# ADC.net
KiCad netlist of a schematic drawn in Altium Designer
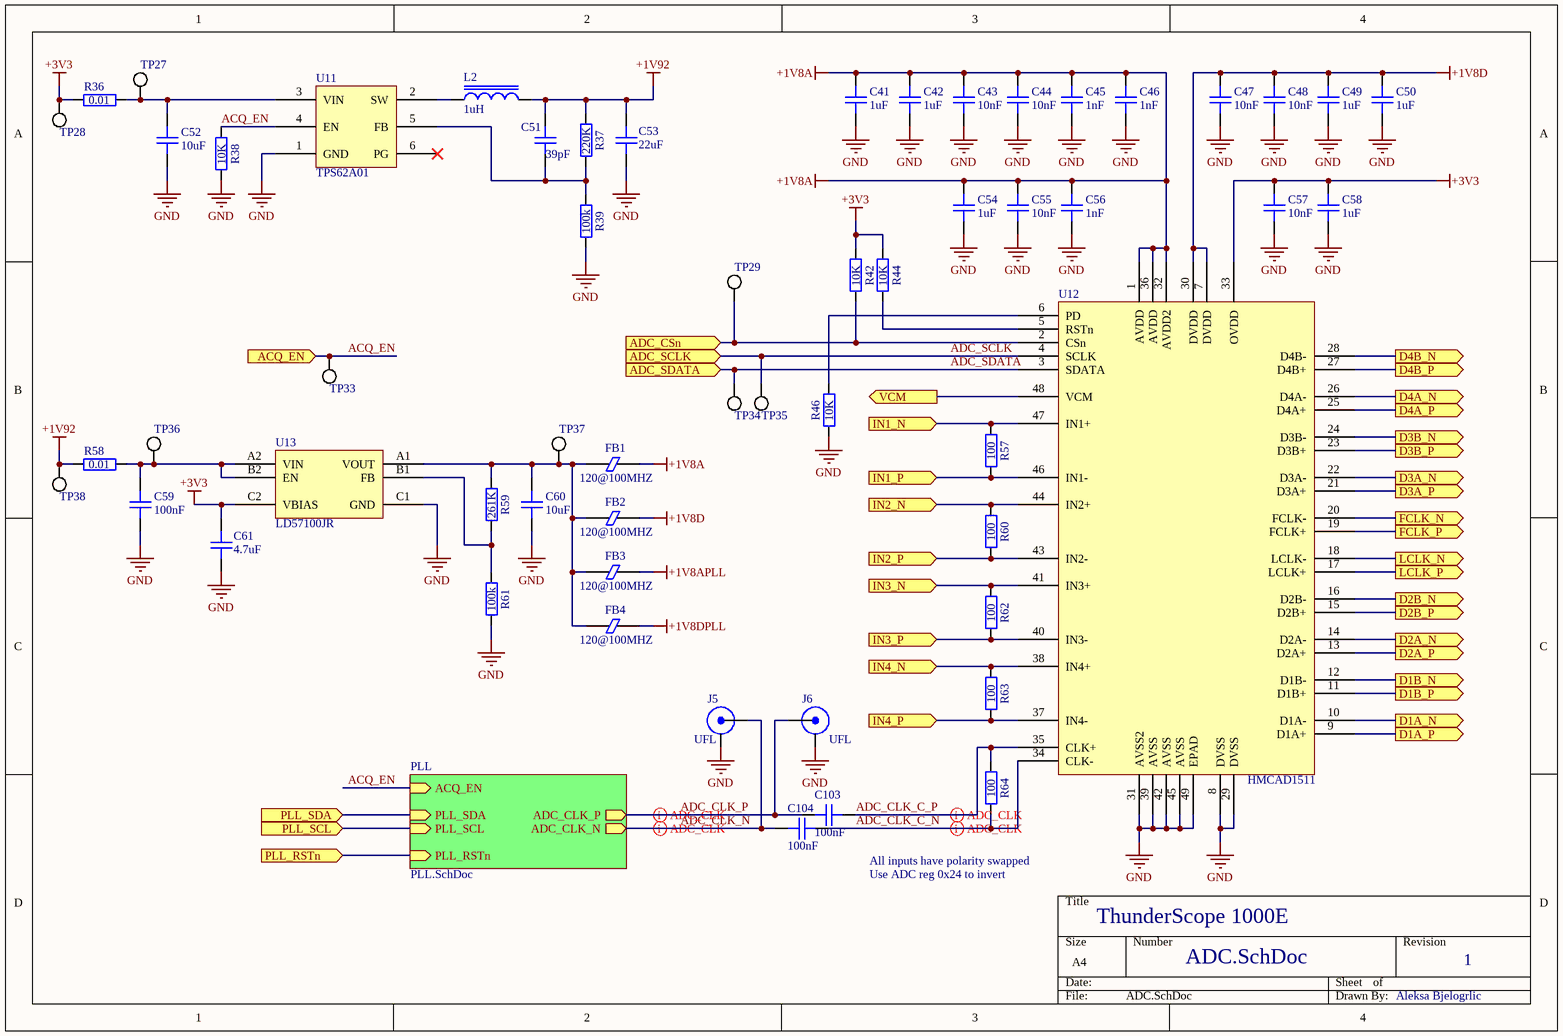
[diagram p0: ADC.SchDoc]

(export (version "E")
  (design (tool "Eeschema 10.0.6"))
  (components
    (comp (ref "C41")
      (value "1uF")
      (footprint "GEN_C_0402")
      (libsource (lib "DSO") (part "CAP 1uF 25V X5R 0402"))
    )
    (comp (ref "C42")
      (value "1uF")
      (footprint "GEN_C_0402")
      (libsource (lib "DSO") (part "CAP 1uF 25V X5R 0402"))
    )
    (comp (ref "C43")
      (value "10nF")
      (footprint "GEN_C_0402")
      (libsource (lib "DSO") (part "CAP 10nF 50V X7R 0402"))
    )
    (comp (ref "C44")
      (value "10nF")
      (footprint "GEN_C_0402")
      (libsource (lib "DSO") (part "CAP 10nF 50V X7R 0402"))
    )
    (comp (ref "C45")
      (value "1nF")
      (footprint "GEN_C_0402")
      (libsource (lib "DSO") (part "CAP 1nF 50V C0G 0402"))
    )
    (comp (ref "C46")
      (value "1nF")
      (footprint "GEN_C_0402")
      (libsource (lib "DSO") (part "CAP 1nF 50V C0G 0402"))
    )
    (comp (ref "C47")
      (value "10nF")
      (footprint "GEN_C_0402")
      (libsource (lib "DSO") (part "CAP 10nF 50V X7R 0402"))
    )
    (comp (ref "C48")
      (value "10nF")
      (footprint "GEN_C_0402")
      (libsource (lib "DSO") (part "CAP 10nF 50V X7R 0402"))
    )
    (comp (ref "C49")
      (value "1uF")
      (footprint "GEN_C_0402")
      (libsource (lib "DSO") (part "CAP 1uF 25V X5R 0402"))
    )
    (comp (ref "C50")
      (value "1uF")
      (footprint "GEN_C_0402")
      (libsource (lib "DSO") (part "CAP 1uF 25V X5R 0402"))
    )
    (comp (ref "C51")
      (value "39pF")
      (footprint "GEN_C_0402")
      (libsource (lib "DSO") (part "CAP 39pF 50V C0G 0402"))
    )
    (comp (ref "C52")
      (value "10uF")
      (footprint "GEN_C_0603")
      (libsource (lib "DSO") (part "CAP 10uF 10V X5R 0603"))
    )
    (comp (ref "C53")
      (value "22uF")
      (footprint "GEN_C_0805")
      (libsource (lib "DSO") (part "CAP 22uF 25V X5R 0805"))
    )
    (comp (ref "C54")
      (value "1uF")
      (footprint "GEN_C_0402")
      (libsource (lib "DSO") (part "CAP 1uF 25V X5R 0402"))
    )
    (comp (ref "C55")
      (value "10nF")
      (footprint "GEN_C_0402")
      (libsource (lib "DSO") (part "CAP 10nF 50V X7R 0402"))
    )
    (comp (ref "C56")
      (value "1nF")
      (footprint "GEN_C_0402")
      (libsource (lib "DSO") (part "CAP 1nF 50V C0G 0402"))
    )
    (comp (ref "C57")
      (value "10nF")
      (footprint "GEN_C_0402")
      (libsource (lib "DSO") (part "CAP 10nF 50V X7R 0402"))
    )
    (comp (ref "C58")
      (value "1uF")
      (footprint "GEN_C_0402")
      (libsource (lib "DSO") (part "CAP 1uF 25V X5R 0402"))
    )
    (comp (ref "C59")
      (value "100nF")
      (footprint "GEN_C_0402")
      (libsource (lib "DSO") (part "CAP 100nF 16V X7R 0402"))
    )
    (comp (ref "C60")
      (value "10uF")
      (footprint "GEN_C_0603")
      (libsource (lib "DSO") (part "CAP 10uF 10V X5R 0603"))
    )
    (comp (ref "C61")
      (value "4.7uF")
      (footprint "GEN_C_0402")
      (libsource (lib "DSO") (part "CAP 4.7uF 6.3V X5R 0402"))
    )
    (comp (ref "C103")
      (value "100nF")
      (footprint "GEN_C_0402")
      (libsource (lib "DSO") (part "CAP 100nF 16V X7R 0402"))
    )
    (comp (ref "C104")
      (value "100nF")
      (footprint "GEN_C_0402")
      (libsource (lib "DSO") (part "CAP 100nF 16V X7R 0402"))
    )
    (comp (ref "FB1")
      (value "120@100MHZ")
      (footprint "GEN_R_0402")
      (libsource (lib "DSO") (part "FERRITE BEAD 120 OHM 0402"))
    )
    (comp (ref "FB2")
      (value "120@100MHZ")
      (footprint "GEN_R_0402")
      (libsource (lib "DSO") (part "FERRITE BEAD 120 OHM 0402"))
    )
    (comp (ref "FB3")
      (value "120@100MHZ")
      (footprint "GEN_R_0402")
      (libsource (lib "DSO") (part "FERRITE BEAD 120 OHM 0402"))
    )
    (comp (ref "FB4")
      (value "120@100MHZ")
      (footprint "GEN_R_0402")
      (libsource (lib "DSO") (part "FERRITE BEAD 120 OHM 0402"))
    )
    (comp (ref "J5") (value "UFL") (footprint "TE_2334884-1") (libsource (lib "DSO") (part "UFL Jack SMD")))
    (comp (ref "J6") (value "UFL") (footprint "TE_2334884-1") (libsource (lib "DSO") (part "UFL Jack SMD")))
    (comp (ref "L2")
      (value "1uH")
      (footprint "GEN_L_1210")
      (libsource (lib "DSO") (part "IND 1uH 3.1A 45 MOHM 1210"))
    )
    (comp (ref "R36")
      (value "0.01")
      (footprint "GEN_R_0603")
      (fields (field (name "TOLERANCE") "1%"))
      (libsource (lib "DSO") (part "RES 0.01 OHM 1% 1/4W 0603"))
    )
    (comp (ref "R37")
      (value "220K")
      (footprint "GEN_R_0402")
      (fields (field (name "TOLERANCE") "1%"))
      (libsource (lib "DSO") (part "RES 220K OHM 1% 1/16W 0402"))
    )
    (comp (ref "R38")
      (value "10K")
      (footprint "GEN_R_0402")
      (fields (field (name "TOLERANCE") "1%"))
      (libsource (lib "") (part "RES 10K OHM 1% 1/10W 0402_1"))
    )
    (comp (ref "R39")
      (value "100k")
      (footprint "GEN_R_0402")
      (fields (field (name "TOLERANCE") "1%"))
      (libsource (lib "DSO") (part "RES 100K OHM 1% 1/10W 0402"))
    )
    (comp (ref "R42")
      (value "10K")
      (footprint "GEN_R_0402")
      (fields (field (name "TOLERANCE") "1%"))
      (libsource (lib "") (part "RES 10K OHM 1% 1/10W 0402_1"))
    )
    (comp (ref "R44")
      (value "10K")
      (footprint "GEN_R_0402")
      (fields (field (name "TOLERANCE") "1%"))
      (libsource (lib "") (part "RES 10K OHM 1% 1/10W 0402_1"))
    )
    (comp (ref "R46")
      (value "10K")
      (footprint "GEN_R_0402")
      (fields (field (name "TOLERANCE") "1%"))
      (libsource (lib "DSO") (part "RES 10K OHM 1% 1/10W 0402"))
    )
    (comp (ref "R57")
      (value "100")
      (footprint "GEN_R_0402")
      (fields (field (name "TOLERANCE") "1%"))
      (libsource (lib "DSO") (part "RES 100 OHM 1% 1/10W 0402"))
    )
    (comp (ref "R58")
      (value "0.01")
      (footprint "GEN_R_0603")
      (fields (field (name "TOLERANCE") "1%"))
      (libsource (lib "DSO") (part "RES 0.01 OHM 1% 1/4W 0603"))
    )
    (comp (ref "R59")
      (value "261K")
      (footprint "GEN_R_0402")
      (fields (field (name "TOLERANCE") "1%"))
      (libsource (lib "DSO") (part "RES 261K OHM 1% 1/16W 0402"))
    )
    (comp (ref "R60")
      (value "100")
      (footprint "GEN_R_0402")
      (fields (field (name "TOLERANCE") "1%"))
      (libsource (lib "DSO") (part "RES 100 OHM 1% 1/10W 0402"))
    )
    (comp (ref "R61")
      (value "100k")
      (footprint "GEN_R_0402")
      (fields (field (name "TOLERANCE") "1%"))
      (libsource (lib "DSO") (part "RES 100K OHM 1% 1/10W 0402"))
    )
    (comp (ref "R62")
      (value "100")
      (footprint "GEN_R_0402")
      (fields (field (name "TOLERANCE") "1%"))
      (libsource (lib "DSO") (part "RES 100 OHM 1% 1/10W 0402"))
    )
    (comp (ref "R63")
      (value "100")
      (footprint "GEN_R_0402")
      (fields (field (name "TOLERANCE") "1%"))
      (libsource (lib "DSO") (part "RES 100 OHM 1% 1/10W 0402"))
    )
    (comp (ref "R64")
      (value "100")
      (footprint "GEN_R_0402")
      (fields (field (name "TOLERANCE") "1%"))
      (libsource (lib "DSO") (part "RES 100 OHM 1% 1/10W 0402"))
    )
    (comp (ref "TP27") (value "PCB") (footprint "GEN_TP_PCB") (libsource (lib "DSO") (part "TP PCB 1mm")))
    (comp (ref "TP28") (value "PCB") (footprint "GEN_TP_PCB") (libsource (lib "DSO") (part "TP PCB 1mm")))
    (comp (ref "TP29") (value "PCB") (footprint "GEN_TP_PCB") (libsource (lib "DSO") (part "TP PCB 1mm")))
    (comp (ref "TP33") (value "PCB") (footprint "GEN_TP_PCB") (libsource (lib "DSO") (part "TP PCB 1mm")))
    (comp (ref "TP34") (value "PCB") (footprint "GEN_TP_PCB") (libsource (lib "DSO") (part "TP PCB 1mm")))
    (comp (ref "TP35") (value "PCB") (footprint "GEN_TP_PCB") (libsource (lib "DSO") (part "TP PCB 1mm")))
    (comp (ref "TP36") (value "PCB") (footprint "GEN_TP_PCB") (libsource (lib "DSO") (part "TP PCB 1mm")))
    (comp (ref "TP37") (value "PCB") (footprint "GEN_TP_PCB") (libsource (lib "DSO") (part "TP PCB 1mm")))
    (comp (ref "TP38") (value "PCB") (footprint "GEN_TP_PCB") (libsource (lib "DSO") (part "TP PCB 1mm")))
    (comp (ref "U11")
      (value "TPS62A01")
      (footprint "TI_SOT563_DRL0006A")
      (libsource (lib "DSO") (part "IC BUCK TPS62A01"))
    )
    (comp (ref "U12")
      (value "HMCAD1511")
      (footprint "AD_QFN48_LP7")
      (libsource (lib "DSO") (part "IC ADC HMCAD1511"))
    )
    (comp (ref "U13")
      (value "LD57100JR")
      (footprint "ST_FlipChip6")
      (libsource (lib "DSO") (part "IC LDO LD57100JR"))
    )
  )
  (nets
    (net (code "1") (name "+1V8A") (class "Default")
      (node (ref "C41") (pin "2") (pinfunction "2_2") (pintype "passive"))
      (node (ref "C42") (pin "2") (pinfunction "2_2") (pintype "passive"))
      (node (ref "C43") (pin "2") (pinfunction "2_2") (pintype "passive"))
      (node (ref "C44") (pin "2") (pinfunction "2_2") (pintype "passive"))
      (node (ref "C45") (pin "2") (pinfunction "2_2") (pintype "passive"))
      (node (ref "C46") (pin "2") (pinfunction "2_2") (pintype "passive"))
      (node (ref "C54") (pin "2") (pinfunction "2_2") (pintype "passive"))
      (node (ref "C55") (pin "2") (pinfunction "2_2") (pintype "passive"))
      (node (ref "C56") (pin "2") (pinfunction "2_2") (pintype "passive"))
      (node (ref "FB1") (pin "2") (pinfunction "2_2") (pintype "passive"))
      (node (ref "U12") (pin "1") (pinfunction "AVDD_1") (pintype "passive"))
      (node (ref "U12") (pin "32") (pinfunction "AVDD2_32") (pintype "passive"))
      (node (ref "U12") (pin "36") (pinfunction "AVDD_36") (pintype "passive"))
    )
    (net (code "2") (name "+1V8APLL") (class "Default")
      (node (ref "FB3") (pin "2") (pinfunction "2_2") (pintype "passive"))
    )
    (net (code "3") (name "+1V8D") (class "Default")
      (node (ref "C47") (pin "2") (pinfunction "2_2") (pintype "passive"))
      (node (ref "C48") (pin "2") (pinfunction "2_2") (pintype "passive"))
      (node (ref "C49") (pin "2") (pinfunction "2_2") (pintype "passive"))
      (node (ref "C50") (pin "2") (pinfunction "2_2") (pintype "passive"))
      (node (ref "FB2") (pin "2") (pinfunction "2_2") (pintype "passive"))
      (node (ref "U12") (pin "30") (pinfunction "DVDD_30") (pintype "passive"))
      (node (ref "U12") (pin "7") (pinfunction "DVDD_7") (pintype "passive"))
    )
    (net (code "4") (name "+1V8DPLL") (class "Default")
      (node (ref "FB4") (pin "2") (pinfunction "2_2") (pintype "passive"))
    )
    (net (code "5") (name "+1V92") (class "Default")
      (node (ref "C51") (pin "2") (pinfunction "2_2") (pintype "passive"))
      (node (ref "C53") (pin "2") (pinfunction "2_2") (pintype "passive"))
      (node (ref "L2") (pin "2") (pinfunction "2_2") (pintype "passive"))
      (node (ref "R37") (pin "2") (pinfunction "2_2") (pintype "passive"))
      (node (ref "R58") (pin "1") (pinfunction "1_1") (pintype "passive"))
      (node (ref "TP38") (pin "1") (pinfunction "1_1") (pintype "passive"))
    )
    (net (code "6") (name "+3V3") (class "Default")
      (node (ref "C57") (pin "2") (pinfunction "2_2") (pintype "passive"))
      (node (ref "C58") (pin "2") (pinfunction "2_2") (pintype "passive"))
      (node (ref "C61") (pin "2") (pinfunction "2_2") (pintype "passive"))
      (node (ref "R36") (pin "1") (pinfunction "1_1") (pintype "passive"))
      (node (ref "R42") (pin "2") (pinfunction "2_2") (pintype "passive"))
      (node (ref "R44") (pin "2") (pinfunction "2_2") (pintype "passive"))
      (node (ref "TP28") (pin "1") (pinfunction "1_1") (pintype "passive"))
      (node (ref "U12") (pin "33") (pinfunction "OVDD_33") (pintype "passive"))
      (node (ref "U13") (pin "C2") (pinfunction "VBIAS_C2") (pintype "passive"))
    )
    (net (code "7") (name "/ACQ_EN") (class "Default")
      (node (ref "R38") (pin "2") (pinfunction "2_2") (pintype "passive"))
      (node (ref "TP33") (pin "1") (pinfunction "1_1") (pintype "passive"))
      (node (ref "U11") (pin "4") (pinfunction "EN_4") (pintype "passive"))
    )
    (net (code "8") (name "/ADC_CLK_C_N") (class "Default")
      (node (ref "C104") (pin "1") (pinfunction "1_1") (pintype "passive"))
      (node (ref "R64") (pin "1") (pinfunction "1_1") (pintype "passive"))
      (node (ref "U12") (pin "34") (pinfunction "CLK-_34") (pintype "passive"))
    )
    (net (code "9") (name "/ADC_CLK_C_P") (class "Default")
      (node (ref "C103") (pin "1") (pinfunction "1_1") (pintype "passive"))
      (node (ref "R64") (pin "2") (pinfunction "2_2") (pintype "passive"))
      (node (ref "U12") (pin "35") (pinfunction "CLK+_35") (pintype "passive"))
    )
    (net (code "10") (name "/ADC_CLK_N") (class "Default")
      (node (ref "C104") (pin "2") (pinfunction "2_2") (pintype "passive"))
      (node (ref "J5") (pin "1") (pinfunction "Signal_1") (pintype "passive"))
    )
    (net (code "11") (name "/ADC_CLK_P") (class "Default")
      (node (ref "C103") (pin "2") (pinfunction "2_2") (pintype "passive"))
      (node (ref "J6") (pin "1") (pinfunction "Signal_1") (pintype "passive"))
    )
    (net (code "12") (name "/ADC_CSn") (class "Default")
      (node (ref "R42") (pin "1") (pinfunction "1_1") (pintype "passive"))
      (node (ref "TP29") (pin "1") (pinfunction "1_1") (pintype "passive"))
      (node (ref "U12") (pin "2") (pinfunction "CSn_2") (pintype "passive"))
    )
    (net (code "13") (name "/ADC_SCLK") (class "Default")
      (node (ref "TP35") (pin "1") (pinfunction "1_1") (pintype "passive"))
      (node (ref "U12") (pin "4") (pinfunction "SCLK_4") (pintype "passive"))
    )
    (net (code "14") (name "/ADC_SDATA") (class "Default")
      (node (ref "TP34") (pin "1") (pinfunction "1_1") (pintype "passive"))
      (node (ref "U12") (pin "3") (pinfunction "SDATA_3") (pintype "passive"))
    )
    (net (code "15") (name "/D1A_N") (class "Default")
      (node (ref "U12") (pin "10") (pinfunction "D1A-_10") (pintype "passive"))
    )
    (net (code "16") (name "/D1A_P") (class "Default")
      (node (ref "U12") (pin "9") (pinfunction "D1A+_9") (pintype "passive"))
    )
    (net (code "17") (name "/D1B_N") (class "Default")
      (node (ref "U12") (pin "12") (pinfunction "D1B-_12") (pintype "passive"))
    )
    (net (code "18") (name "/D1B_P") (class "Default")
      (node (ref "U12") (pin "11") (pinfunction "D1B+_11") (pintype "passive"))
    )
    (net (code "19") (name "/D2A_N") (class "Default")
      (node (ref "U12") (pin "14") (pinfunction "D2A-_14") (pintype "passive"))
    )
    (net (code "20") (name "/D2A_P") (class "Default")
      (node (ref "U12") (pin "13") (pinfunction "D2A+_13") (pintype "passive"))
    )
    (net (code "21") (name "/D2B_N") (class "Default")
      (node (ref "U12") (pin "16") (pinfunction "D2B-_16") (pintype "passive"))
    )
    (net (code "22") (name "/D2B_P") (class "Default")
      (node (ref "U12") (pin "15") (pinfunction "D2B+_15") (pintype "passive"))
    )
    (net (code "23") (name "/D3A_N") (class "Default")
      (node (ref "U12") (pin "22") (pinfunction "D3A-_22") (pintype "passive"))
    )
    (net (code "24") (name "/D3A_P") (class "Default")
      (node (ref "U12") (pin "21") (pinfunction "D3A+_21") (pintype "passive"))
    )
    (net (code "25") (name "/D3B_N") (class "Default")
      (node (ref "U12") (pin "24") (pinfunction "D3B-_24") (pintype "passive"))
    )
    (net (code "26") (name "/D3B_P") (class "Default")
      (node (ref "U12") (pin "23") (pinfunction "D3B+_23") (pintype "passive"))
    )
    (net (code "27") (name "/D4A_N") (class "Default")
      (node (ref "U12") (pin "26") (pinfunction "D4A-_26") (pintype "passive"))
    )
    (net (code "28") (name "/D4A_P") (class "Default")
      (node (ref "U12") (pin "25") (pinfunction "D4A+_25") (pintype "passive"))
    )
    (net (code "29") (name "/D4B_N") (class "Default")
      (node (ref "U12") (pin "28") (pinfunction "D4B-_28") (pintype "passive"))
    )
    (net (code "30") (name "/D4B_P") (class "Default")
      (node (ref "U12") (pin "27") (pinfunction "D4B+_27") (pintype "passive"))
    )
    (net (code "31") (name "/FCLK_N") (class "Default")
      (node (ref "U12") (pin "20") (pinfunction "FCLK-_20") (pintype "passive"))
    )
    (net (code "32") (name "/FCLK_P") (class "Default")
      (node (ref "U12") (pin "19") (pinfunction "FCLK+_19") (pintype "passive"))
    )
    (net (code "33") (name "/IN1_N") (class "Default")
      (node (ref "R57") (pin "2") (pinfunction "2_2") (pintype "passive"))
      (node (ref "U12") (pin "47") (pinfunction "IN1+_47") (pintype "passive"))
    )
    (net (code "34") (name "/IN1_P") (class "Default")
      (node (ref "R57") (pin "1") (pinfunction "1_1") (pintype "passive"))
      (node (ref "U12") (pin "46") (pinfunction "IN1-_46") (pintype "passive"))
    )
    (net (code "35") (name "/IN2_N") (class "Default")
      (node (ref "R60") (pin "2") (pinfunction "2_2") (pintype "passive"))
      (node (ref "U12") (pin "44") (pinfunction "IN2+_44") (pintype "passive"))
    )
    (net (code "36") (name "/IN2_P") (class "Default")
      (node (ref "R60") (pin "1") (pinfunction "1_1") (pintype "passive"))
      (node (ref "U12") (pin "43") (pinfunction "IN2-_43") (pintype "passive"))
    )
    (net (code "37") (name "/IN3_N") (class "Default")
      (node (ref "R62") (pin "2") (pinfunction "2_2") (pintype "passive"))
      (node (ref "U12") (pin "41") (pinfunction "IN3+_41") (pintype "passive"))
    )
    (net (code "38") (name "/IN3_P") (class "Default")
      (node (ref "R62") (pin "1") (pinfunction "1_1") (pintype "passive"))
      (node (ref "U12") (pin "40") (pinfunction "IN3-_40") (pintype "passive"))
    )
    (net (code "39") (name "/IN4_N") (class "Default")
      (node (ref "R63") (pin "2") (pinfunction "2_2") (pintype "passive"))
      (node (ref "U12") (pin "38") (pinfunction "IN4+_38") (pintype "passive"))
    )
    (net (code "40") (name "/IN4_P") (class "Default")
      (node (ref "R63") (pin "1") (pinfunction "1_1") (pintype "passive"))
      (node (ref "U12") (pin "37") (pinfunction "IN4-_37") (pintype "passive"))
    )
    (net (code "41") (name "/LCLK_N") (class "Default")
      (node (ref "U12") (pin "18") (pinfunction "LCLK-_18") (pintype "passive"))
    )
    (net (code "42") (name "/LCLK_P") (class "Default")
      (node (ref "U12") (pin "17") (pinfunction "LCLK+_17") (pintype "passive"))
    )
    (net (code "46") (name "/VCM") (class "Default")
      (node (ref "U12") (pin "48") (pinfunction "VCM_48") (pintype "passive"))
    )
    (net (code "47") (name "GND") (class "Default")
      (node (ref "C41") (pin "1") (pinfunction "1_1") (pintype "passive"))
      (node (ref "C42") (pin "1") (pinfunction "1_1") (pintype "passive"))
      (node (ref "C43") (pin "1") (pinfunction "1_1") (pintype "passive"))
      (node (ref "C44") (pin "1") (pinfunction "1_1") (pintype "passive"))
      (node (ref "C45") (pin "1") (pinfunction "1_1") (pintype "passive"))
      (node (ref "C46") (pin "1") (pinfunction "1_1") (pintype "passive"))
      (node (ref "C47") (pin "1") (pinfunction "1_1") (pintype "passive"))
      (node (ref "C48") (pin "1") (pinfunction "1_1") (pintype "passive"))
      (node (ref "C49") (pin "1") (pinfunction "1_1") (pintype "passive"))
      (node (ref "C50") (pin "1") (pinfunction "1_1") (pintype "passive"))
      (node (ref "C52") (pin "1") (pinfunction "1_1") (pintype "passive"))
      (node (ref "C53") (pin "1") (pinfunction "1_1") (pintype "passive"))
      (node (ref "C54") (pin "1") (pinfunction "1_1") (pintype "passive"))
      (node (ref "C55") (pin "1") (pinfunction "1_1") (pintype "passive"))
      (node (ref "C56") (pin "1") (pinfunction "1_1") (pintype "passive"))
      (node (ref "C57") (pin "1") (pinfunction "1_1") (pintype "passive"))
      (node (ref "C58") (pin "1") (pinfunction "1_1") (pintype "passive"))
      (node (ref "C59") (pin "1") (pinfunction "1_1") (pintype "passive"))
      (node (ref "C60") (pin "1") (pinfunction "1_1") (pintype "passive"))
      (node (ref "C61") (pin "1") (pinfunction "1_1") (pintype "passive"))
      (node (ref "J5") (pin "2") (pinfunction "SHIELD_2") (pintype "passive"))
      (node (ref "J6") (pin "2") (pinfunction "SHIELD_2") (pintype "passive"))
      (node (ref "R38") (pin "1") (pinfunction "1_1") (pintype "passive"))
      (node (ref "R39") (pin "1") (pinfunction "1_1") (pintype "passive"))
      (node (ref "R46") (pin "2") (pinfunction "2_2") (pintype "passive"))
      (node (ref "R61") (pin "1") (pinfunction "1_1") (pintype "passive"))
      (node (ref "U11") (pin "1") (pinfunction "GND_1") (pintype "power_in"))
      (node (ref "U12") (pin "29") (pinfunction "DVSS_29") (pintype "passive"))
      (node (ref "U12") (pin "31") (pinfunction "AVSS2_31") (pintype "passive"))
      (node (ref "U12") (pin "39") (pinfunction "AVSS_39") (pintype "passive"))
      (node (ref "U12") (pin "42") (pinfunction "AVSS_42") (pintype "passive"))
      (node (ref "U12") (pin "45") (pinfunction "AVSS_45") (pintype "passive"))
      (node (ref "U12") (pin "49") (pinfunction "EPAD_49") (pintype "passive"))
      (node (ref "U12") (pin "8") (pinfunction "DVSS_8") (pintype "passive"))
      (node (ref "U13") (pin "C1") (pinfunction "GND_C1") (pintype "passive"))
    )
    (net (code "48") (name "Net-(U11-FB)") (class "Default")
      (node (ref "C51") (pin "1") (pinfunction "1_1") (pintype "passive"))
      (node (ref "R37") (pin "1") (pinfunction "1_1") (pintype "passive"))
      (node (ref "R39") (pin "2") (pinfunction "2_2") (pintype "passive"))
      (node (ref "U11") (pin "5") (pinfunction "FB_5") (pintype "passive"))
    )
    (net (code "49") (name "Net-(U11-SW)") (class "Default")
      (node (ref "L2") (pin "1") (pinfunction "1_1") (pintype "passive"))
      (node (ref "U11") (pin "2") (pinfunction "SW_2") (pintype "passive"))
    )
    (net (code "50") (name "Net-(U11-VIN)") (class "Default")
      (node (ref "C52") (pin "2") (pinfunction "2_2") (pintype "passive"))
      (node (ref "R36") (pin "2") (pinfunction "2_2") (pintype "passive"))
      (node (ref "TP27") (pin "1") (pinfunction "1_1") (pintype "passive"))
      (node (ref "U11") (pin "3") (pinfunction "VIN_3") (pintype "power_in"))
    )
    (net (code "51") (name "Net-(U12-PD)") (class "Default")
      (node (ref "R46") (pin "1") (pinfunction "1_1") (pintype "passive"))
      (node (ref "U12") (pin "6") (pinfunction "PD_6") (pintype "passive"))
    )
    (net (code "52") (name "Net-(U12-RSTn)") (class "Default")
      (node (ref "R44") (pin "1") (pinfunction "1_1") (pintype "passive"))
      (node (ref "U12") (pin "5") (pinfunction "RSTn_5") (pintype "passive"))
    )
    (net (code "53") (name "Net-(U13-EN)") (class "Default")
      (node (ref "C59") (pin "2") (pinfunction "2_2") (pintype "passive"))
      (node (ref "R58") (pin "2") (pinfunction "2_2") (pintype "passive"))
      (node (ref "TP36") (pin "1") (pinfunction "1_1") (pintype "passive"))
      (node (ref "U13") (pin "A2") (pinfunction "VIN_A2") (pintype "passive"))
      (node (ref "U13") (pin "B2") (pinfunction "EN_B2") (pintype "passive"))
    )
    (net (code "54") (name "Net-(U13-FB)") (class "Default")
      (node (ref "R59") (pin "1") (pinfunction "1_1") (pintype "passive"))
      (node (ref "R61") (pin "2") (pinfunction "2_2") (pintype "passive"))
      (node (ref "U13") (pin "B1") (pinfunction "FB_B1") (pintype "passive"))
    )
    (net (code "55") (name "Net-(U13-VOUT)") (class "Default")
      (node (ref "C60") (pin "2") (pinfunction "2_2") (pintype "passive"))
      (node (ref "FB1") (pin "1") (pinfunction "1_1") (pintype "passive"))
      (node (ref "FB2") (pin "1") (pinfunction "1_1") (pintype "passive"))
      (node (ref "FB3") (pin "1") (pinfunction "1_1") (pintype "passive"))
      (node (ref "FB4") (pin "1") (pinfunction "1_1") (pintype "passive"))
      (node (ref "R59") (pin "2") (pinfunction "2_2") (pintype "passive"))
      (node (ref "TP37") (pin "1") (pinfunction "1_1") (pintype "passive"))
      (node (ref "U13") (pin "A1") (pinfunction "VOUT_A1") (pintype "passive"))
    )
    (net (code "56") (name "unconnected-(U11-PG-Pad6)") (class "Default")
      (node (ref "U11") (pin "6") (pinfunction "PG_6") (pintype "passive+no_connect"))
    )
  )
)
